# yabc.net
KiCad netlist of a schematic drawn in EAGLE
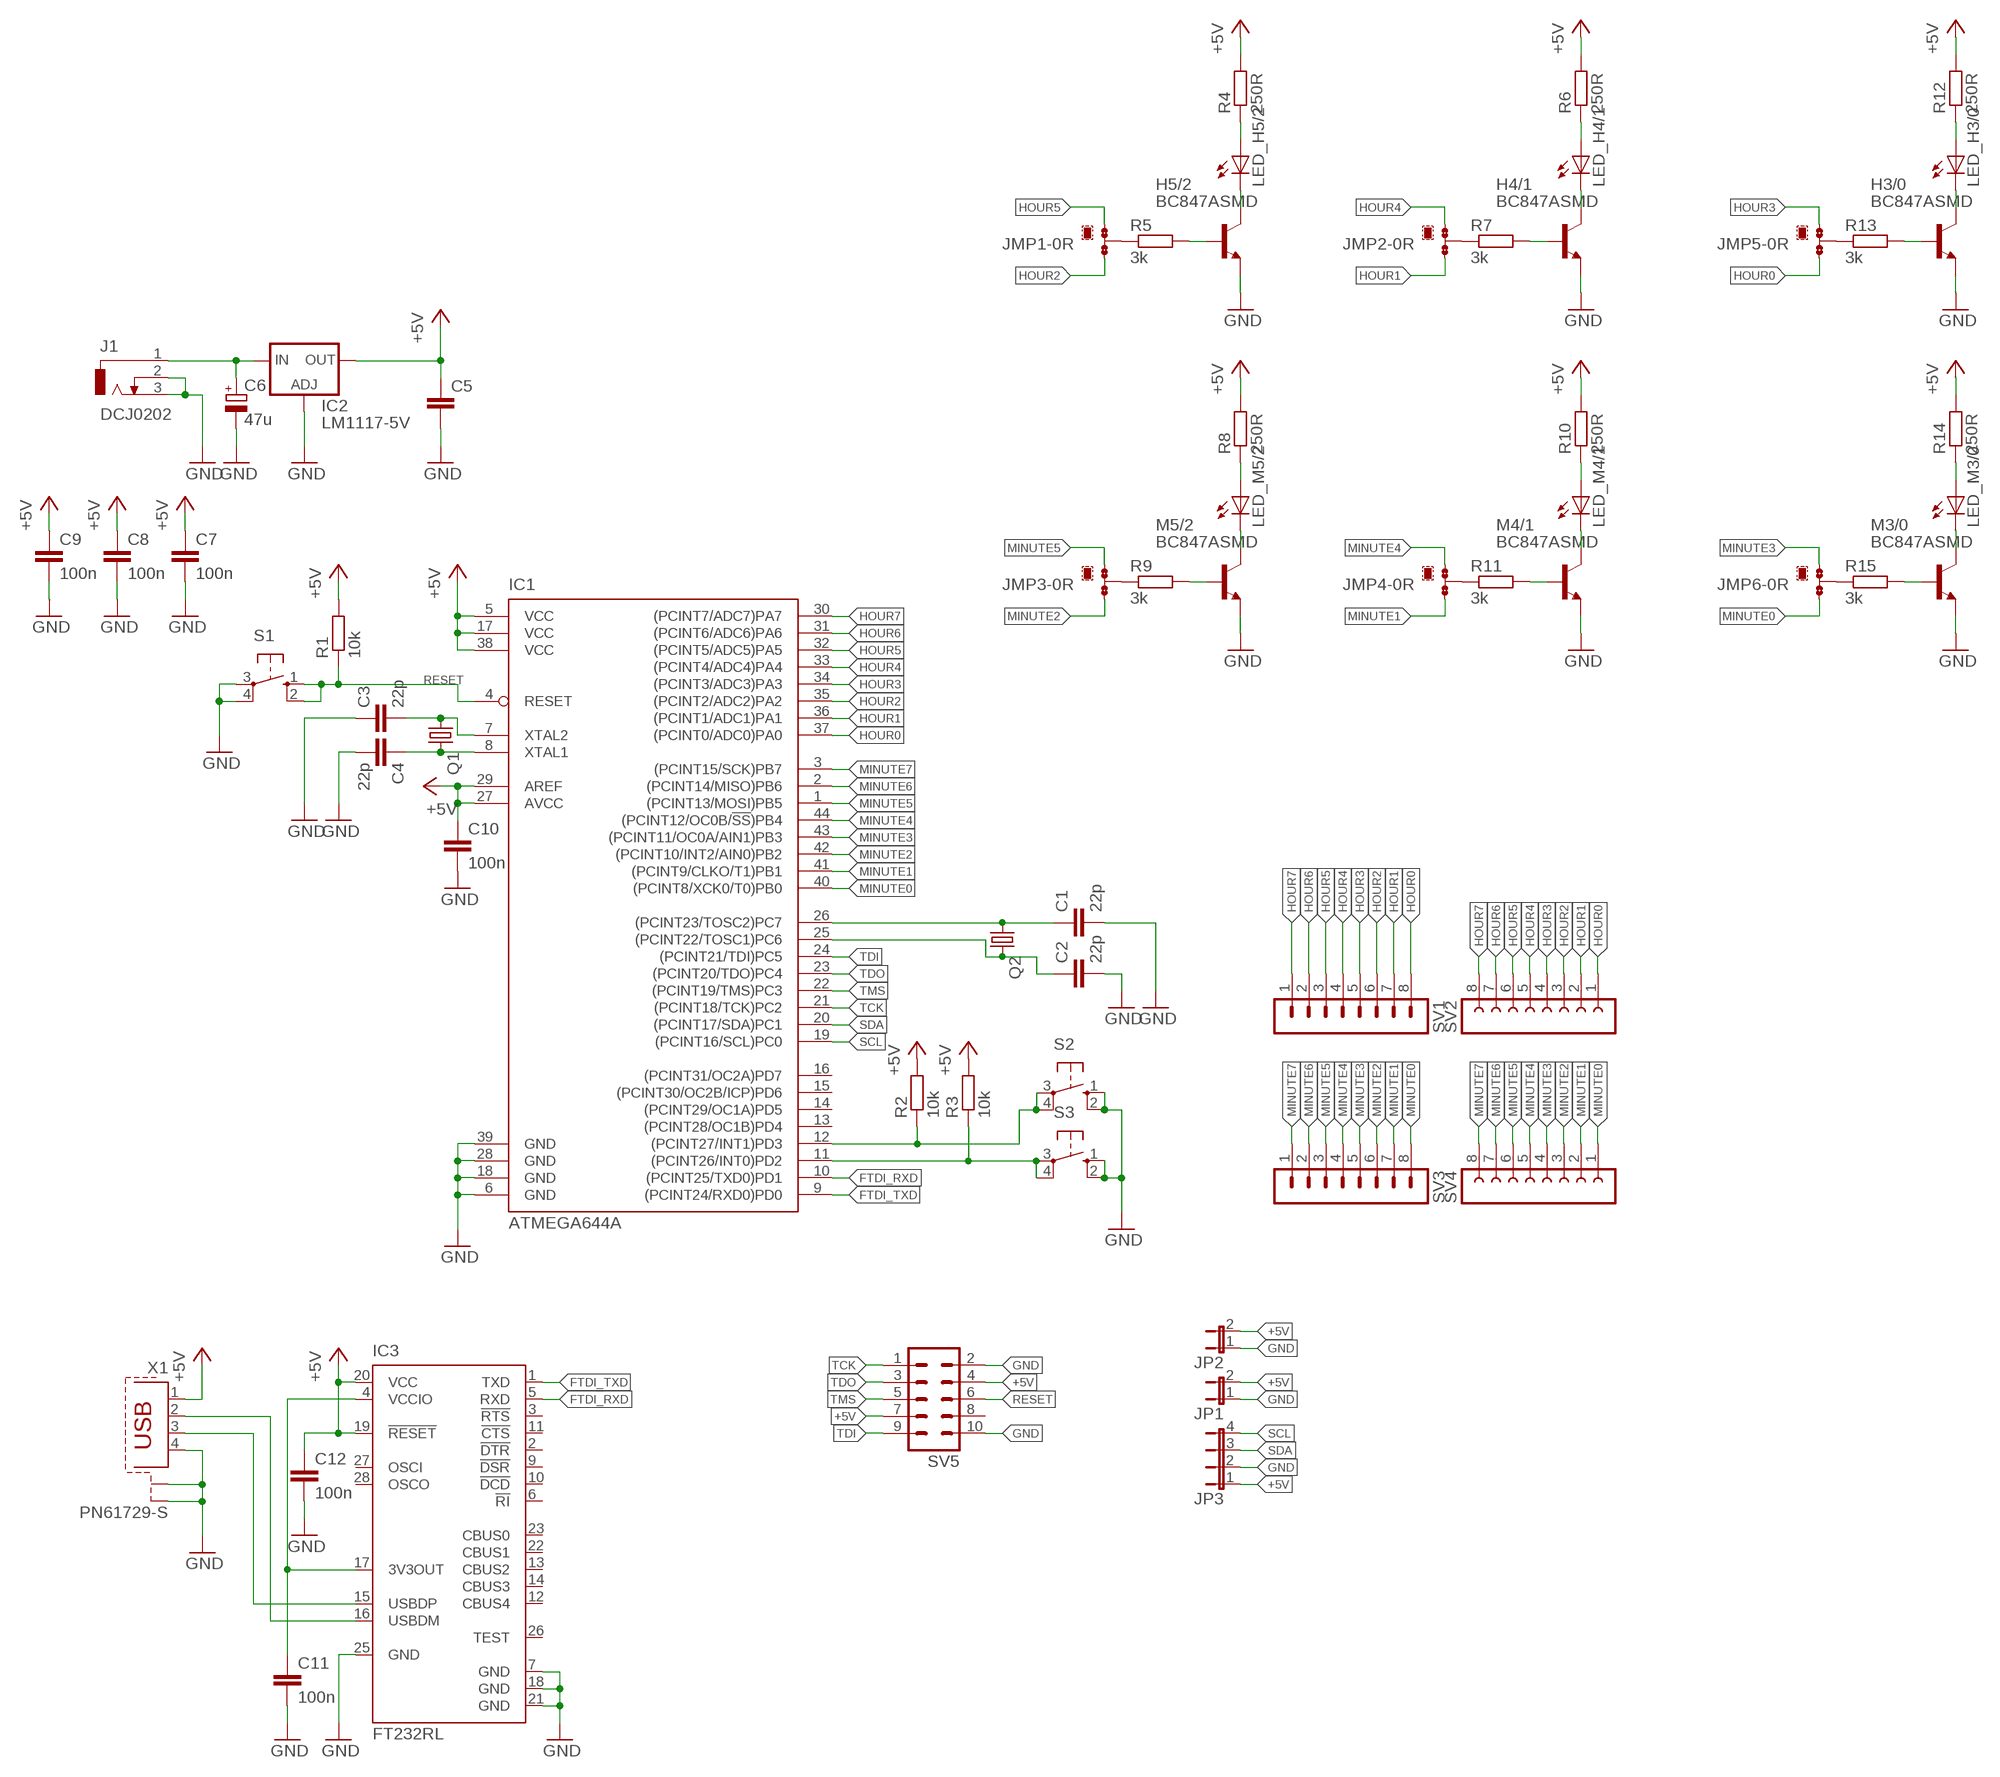
[diagram p0: schematic, sheet 1]

(export (version "E")
  (design (tool "Eeschema 10.0.6"))
  (components
    (comp (ref "C1")
      (value "22p")
      (footprint "eagle-import:C0603")
      (libsource (lib "eagle-import") (part "C-EUC0603"))
    )
    (comp (ref "C2")
      (value "22p")
      (footprint "eagle-import:C0603")
      (libsource (lib "eagle-import") (part "C-EUC0603"))
    )
    (comp (ref "C3")
      (value "22p")
      (footprint "eagle-import:C0603")
      (libsource (lib "eagle-import") (part "C-EUC0603"))
    )
    (comp (ref "C4")
      (value "22p")
      (footprint "eagle-import:C0603")
      (libsource (lib "eagle-import") (part "C-EUC0603"))
    )
    (comp (ref "C5")
      (value "C-EUC0805")
      (footprint "eagle-import:C0805")
      (libsource (lib "eagle-import") (part "C-EUC0805"))
    )
    (comp (ref "C6")
      (value "47u")
      (footprint "eagle-import:SANYO-OSCON_SMD_B6")
      (libsource (lib "eagle-import") (part "CPOL-EUSANYO_SMD_B6"))
    )
    (comp (ref "C7")
      (value "100n")
      (footprint "eagle-import:C0603")
      (libsource (lib "eagle-import") (part "C-EUC0603"))
    )
    (comp (ref "C8")
      (value "100n")
      (footprint "eagle-import:C0603")
      (libsource (lib "eagle-import") (part "C-EUC0603"))
    )
    (comp (ref "C9")
      (value "100n")
      (footprint "eagle-import:C0603")
      (libsource (lib "eagle-import") (part "C-EUC0603"))
    )
    (comp (ref "C10")
      (value "100n")
      (footprint "eagle-import:C0603")
      (libsource (lib "eagle-import") (part "C-EUC0603"))
    )
    (comp (ref "C11")
      (value "100n")
      (footprint "eagle-import:C0603")
      (libsource (lib "eagle-import") (part "C-EUC0603"))
    )
    (comp (ref "C12")
      (value "100n")
      (footprint "eagle-import:C0603")
      (libsource (lib "eagle-import") (part "C-EUC0603"))
    )
    (comp (ref "H3/0")
      (value "BC847ASMD")
      (footprint "eagle-import:SOT23")
      (libsource (lib "eagle-import") (part "BC847SMDA"))
    )
    (comp (ref "H4/1")
      (value "BC847ASMD")
      (footprint "eagle-import:SOT23")
      (libsource (lib "eagle-import") (part "BC847SMDA"))
    )
    (comp (ref "H5/2")
      (value "BC847ASMD")
      (footprint "eagle-import:SOT23")
      (libsource (lib "eagle-import") (part "BC847SMDA"))
    )
    (comp (ref "IC1")
      (value "ATMEGA644A")
      (footprint "eagle-import:TQFP44")
      (fields (field (name "MPN") "ATMEGA644PV-10AU"))
      (libsource (lib "eagle-import") (part "ATMEGA644A"))
    )
    (comp (ref "IC2")
      (value "LM1117-5V")
      (footprint "eagle-import:SOT223")
      (libsource (lib "eagle-import") (part "LM317?MBSTT3"))
    )
    (comp (ref "IC3")
      (value "FT232RL")
      (footprint "eagle-import:SSOP28")
      (libsource (lib "eagle-import") (part "FT232RL"))
    )
    (comp (ref "J1")
      (value "DCJ0202")
      (footprint "eagle-import:DCJ0202")
      (libsource (lib "eagle-import") (part "DCJ0202"))
    )
    (comp (ref "JMP1")
      (value "0R-JUMPC")
      (footprint "eagle-import:C0R-JMP")
      (libsource (lib "eagle-import") (part "0R-JUMPC"))
    )
    (comp (ref "JMP2")
      (value "0R-JUMPC")
      (footprint "eagle-import:C0R-JMP")
      (libsource (lib "eagle-import") (part "0R-JUMPC"))
    )
    (comp (ref "JMP3")
      (value "0R-JUMPC")
      (footprint "eagle-import:C0R-JMP")
      (libsource (lib "eagle-import") (part "0R-JUMPC"))
    )
    (comp (ref "JMP4")
      (value "0R-JUMPC")
      (footprint "eagle-import:C0R-JMP")
      (libsource (lib "eagle-import") (part "0R-JUMPC"))
    )
    (comp (ref "JMP5")
      (value "0R-JUMPC")
      (footprint "eagle-import:C0R-JMP")
      (libsource (lib "eagle-import") (part "0R-JUMPC"))
    )
    (comp (ref "JMP6")
      (value "0R-JUMPC")
      (footprint "eagle-import:C0R-JMP")
      (libsource (lib "eagle-import") (part "0R-JUMPC"))
    )
    (comp (ref "JP1")
      (value "JP1E")
      (footprint "eagle-import:JP1")
      (libsource (lib "eagle-import") (part "JP1E"))
    )
    (comp (ref "JP2")
      (value "JP1E")
      (footprint "eagle-import:JP1")
      (libsource (lib "eagle-import") (part "JP1E"))
    )
    (comp (ref "JP3")
      (value "JP4E")
      (footprint "eagle-import:JP4")
      (libsource (lib "eagle-import") (part "JP4E"))
    )
    (comp (ref "LED_H3/0")
      (value "LED10MM")
      (footprint "eagle-import:LED10MM")
      (libsource (lib "eagle-import") (part "LED10MM"))
    )
    (comp (ref "LED_H4/1")
      (value "LED10MM")
      (footprint "eagle-import:LED10MM")
      (libsource (lib "eagle-import") (part "LED10MM"))
    )
    (comp (ref "LED_H5/2")
      (value "LED10MM")
      (footprint "eagle-import:LED10MM")
      (libsource (lib "eagle-import") (part "LED10MM"))
    )
    (comp (ref "LED_M3/0")
      (value "LED10MM")
      (footprint "eagle-import:LED10MM")
      (libsource (lib "eagle-import") (part "LED10MM"))
    )
    (comp (ref "LED_M4/1")
      (value "LED10MM")
      (footprint "eagle-import:LED10MM")
      (libsource (lib "eagle-import") (part "LED10MM"))
    )
    (comp (ref "LED_M5/2")
      (value "LED10MM")
      (footprint "eagle-import:LED10MM")
      (libsource (lib "eagle-import") (part "LED10MM"))
    )
    (comp (ref "M3/0")
      (value "BC847ASMD")
      (footprint "eagle-import:SOT23")
      (libsource (lib "eagle-import") (part "BC847SMDA"))
    )
    (comp (ref "M4/1")
      (value "BC847ASMD")
      (footprint "eagle-import:SOT23")
      (libsource (lib "eagle-import") (part "BC847SMDA"))
    )
    (comp (ref "M5/2")
      (value "BC847ASMD")
      (footprint "eagle-import:SOT23")
      (libsource (lib "eagle-import") (part "BC847SMDA"))
    )
    (comp (ref "Q1")
      (value "CRYSTALHC49UP")
      (footprint "eagle-import:HC49UP")
      (libsource (lib "eagle-import") (part "CRYSTALHC49UP"))
    )
    (comp (ref "Q2")
      (value "CRYSTALTC26H")
      (footprint "eagle-import:TC26H")
      (libsource (lib "eagle-import") (part "CRYSTALTC26H"))
    )
    (comp (ref "R1")
      (value "10k")
      (footprint "eagle-import:R0603")
      (libsource (lib "eagle-import") (part "R-EU_R0603"))
    )
    (comp (ref "R2")
      (value "10k")
      (footprint "eagle-import:R0603")
      (libsource (lib "eagle-import") (part "R-EU_R0603"))
    )
    (comp (ref "R3")
      (value "10k")
      (footprint "eagle-import:R0603")
      (libsource (lib "eagle-import") (part "R-EU_R0603"))
    )
    (comp (ref "R4")
      (value "250R")
      (footprint "eagle-import:R0805")
      (libsource (lib "eagle-import") (part "R-EU_R0805"))
    )
    (comp (ref "R5")
      (value "3k")
      (footprint "eagle-import:R0603")
      (libsource (lib "eagle-import") (part "R-EU_R0603"))
    )
    (comp (ref "R6")
      (value "250R")
      (footprint "eagle-import:R0805")
      (libsource (lib "eagle-import") (part "R-EU_R0805"))
    )
    (comp (ref "R7")
      (value "3k")
      (footprint "eagle-import:R0603")
      (libsource (lib "eagle-import") (part "R-EU_R0603"))
    )
    (comp (ref "R8")
      (value "250R")
      (footprint "eagle-import:R0805")
      (libsource (lib "eagle-import") (part "R-EU_R0805"))
    )
    (comp (ref "R9")
      (value "3k")
      (footprint "eagle-import:R0603")
      (libsource (lib "eagle-import") (part "R-EU_R0603"))
    )
    (comp (ref "R10")
      (value "250R")
      (footprint "eagle-import:R0805")
      (libsource (lib "eagle-import") (part "R-EU_R0805"))
    )
    (comp (ref "R11")
      (value "3k")
      (footprint "eagle-import:R0603")
      (libsource (lib "eagle-import") (part "R-EU_R0603"))
    )
    (comp (ref "R12")
      (value "250R")
      (footprint "eagle-import:R0805")
      (libsource (lib "eagle-import") (part "R-EU_R0805"))
    )
    (comp (ref "R13")
      (value "3k")
      (footprint "eagle-import:R0603")
      (libsource (lib "eagle-import") (part "R-EU_R0603"))
    )
    (comp (ref "R14")
      (value "250R")
      (footprint "eagle-import:R0805")
      (libsource (lib "eagle-import") (part "R-EU_R0805"))
    )
    (comp (ref "R15")
      (value "3k")
      (footprint "eagle-import:R0603")
      (libsource (lib "eagle-import") (part "R-EU_R0603"))
    )
    (comp (ref "S1")
      (value "10-XX")
      (footprint "eagle-import:B3F-10XX")
      (fields (field (name "MPN") "B3F-1000"))
      (libsource (lib "eagle-import") (part "10-XX"))
    )
    (comp (ref "S2")
      (value "10-XX")
      (footprint "eagle-import:B3F-10XX")
      (fields (field (name "MPN") "B3F-1000"))
      (libsource (lib "eagle-import") (part "10-XX"))
    )
    (comp (ref "S3")
      (value "10-XX")
      (footprint "eagle-import:B3F-10XX")
      (fields (field (name "MPN") "B3F-1000"))
      (libsource (lib "eagle-import") (part "10-XX"))
    )
    (comp (ref "SV1")
      (value "MA08-1W")
      (footprint "eagle-import:MA08-1W")
      (libsource (lib "eagle-import") (part "MA08-1W"))
    )
    (comp (ref "SV2")
      (value "FE08W")
      (footprint "eagle-import:FE08W")
      (libsource (lib "eagle-import") (part "FE08W"))
    )
    (comp (ref "SV3")
      (value "MA08-1W")
      (footprint "eagle-import:MA08-1W")
      (libsource (lib "eagle-import") (part "MA08-1W"))
    )
    (comp (ref "SV4")
      (value "FE08W")
      (footprint "eagle-import:FE08W")
      (libsource (lib "eagle-import") (part "FE08W"))
    )
    (comp (ref "SV5")
      (value "ML10")
      (footprint "eagle-import:ML10")
      (libsource (lib "eagle-import") (part "ML10"))
    )
    (comp (ref "X1")
      (value "PN61729-S")
      (footprint "eagle-import:PN61729-S")
      (libsource (lib "eagle-import") (part "PN61729-S"))
    )
  )
  (nets
    (net (code "1") (name "+5V") (class "Default")
      (node (ref "C10") (pin "1") (pinfunction "1_1") (pintype "passive"))
      (node (ref "C12") (pin "1") (pinfunction "1_1") (pintype "passive"))
      (node (ref "C5") (pin "1") (pinfunction "1_1") (pintype "passive"))
      (node (ref "C7") (pin "1") (pinfunction "1_1") (pintype "passive"))
      (node (ref "C8") (pin "1") (pinfunction "1_1") (pintype "passive"))
      (node (ref "C9") (pin "1") (pinfunction "1_1") (pintype "passive"))
      (node (ref "IC1") (pin "17") (pinfunction "VCC_17") (pintype "power_in"))
      (node (ref "IC1") (pin "27") (pinfunction "AVCC_27") (pintype "power_in"))
      (node (ref "IC1") (pin "29") (pinfunction "AREF_29") (pintype "passive"))
      (node (ref "IC1") (pin "38") (pinfunction "VCC_38") (pintype "power_in"))
      (node (ref "IC1") (pin "5") (pinfunction "VCC_5") (pintype "power_in"))
      (node (ref "IC2") (pin "4") (pinfunction "OUT_4") (pintype "passive"))
      (node (ref "IC3") (pin "19") (pinfunction "~{RESET}_19") (pintype "input"))
      (node (ref "IC3") (pin "20") (pinfunction "VCC_20") (pintype "power_in"))
      (node (ref "JP1") (pin "2") (pinfunction "2_2") (pintype "passive"))
      (node (ref "JP2") (pin "2") (pinfunction "2_2") (pintype "passive"))
      (node (ref "JP3") (pin "1") (pinfunction "1_1") (pintype "passive"))
      (node (ref "R1") (pin "2") (pinfunction "2_2") (pintype "passive"))
      (node (ref "R10") (pin "2") (pinfunction "2_2") (pintype "passive"))
      (node (ref "R12") (pin "2") (pinfunction "2_2") (pintype "passive"))
      (node (ref "R14") (pin "2") (pinfunction "2_2") (pintype "passive"))
      (node (ref "R2") (pin "2") (pinfunction "2_2") (pintype "passive"))
      (node (ref "R3") (pin "2") (pinfunction "2_2") (pintype "passive"))
      (node (ref "R4") (pin "2") (pinfunction "2_2") (pintype "passive"))
      (node (ref "R6") (pin "2") (pinfunction "2_2") (pintype "passive"))
      (node (ref "R8") (pin "2") (pinfunction "2_2") (pintype "passive"))
      (node (ref "SV5") (pin "4") (pinfunction "4_4") (pintype "passive"))
      (node (ref "SV5") (pin "7") (pinfunction "7_7") (pintype "passive"))
      (node (ref "X1") (pin "1") (pinfunction "1_1") (pintype "passive"))
    )
    (net (code "2") (name "FTDI_RXD") (class "Default")
      (node (ref "IC1") (pin "10") (pinfunction "(PCINT25/TXD0)PD1_10") (pintype "bidirectional"))
      (node (ref "IC3") (pin "5") (pinfunction "RXD_5") (pintype "input"))
    )
    (net (code "3") (name "FTDI_TXD") (class "Default")
      (node (ref "IC1") (pin "9") (pinfunction "(PCINT24/RXD0)PD0_9") (pintype "bidirectional"))
      (node (ref "IC3") (pin "1") (pinfunction "TXD_1") (pintype "output"))
    )
    (net (code "4") (name "GND") (class "Default")
      (node (ref "C1") (pin "2") (pinfunction "2_2") (pintype "passive"))
      (node (ref "C10") (pin "2") (pinfunction "2_2") (pintype "passive"))
      (node (ref "C11") (pin "2") (pinfunction "2_2") (pintype "passive"))
      (node (ref "C12") (pin "2") (pinfunction "2_2") (pintype "passive"))
      (node (ref "C2") (pin "2") (pinfunction "2_2") (pintype "passive"))
      (node (ref "C3") (pin "1") (pinfunction "1_1") (pintype "passive"))
      (node (ref "C4") (pin "2") (pinfunction "2_2") (pintype "passive"))
      (node (ref "C5") (pin "2") (pinfunction "2_2") (pintype "passive"))
      (node (ref "C6") (pin "-") (pinfunction "-_-") (pintype "passive"))
      (node (ref "C7") (pin "2") (pinfunction "2_2") (pintype "passive"))
      (node (ref "C8") (pin "2") (pinfunction "2_2") (pintype "passive"))
      (node (ref "C9") (pin "2") (pinfunction "2_2") (pintype "passive"))
      (node (ref "H3/0") (pin "2") (pinfunction "E_2") (pintype "passive"))
      (node (ref "H4/1") (pin "2") (pinfunction "E_2") (pintype "passive"))
      (node (ref "H5/2") (pin "2") (pinfunction "E_2") (pintype "passive"))
      (node (ref "IC1") (pin "18") (pinfunction "GND_18") (pintype "power_in"))
      (node (ref "IC1") (pin "28") (pinfunction "GND_28") (pintype "power_in"))
      (node (ref "IC1") (pin "39") (pinfunction "GND_39") (pintype "power_in"))
      (node (ref "IC1") (pin "6") (pinfunction "GND_6") (pintype "power_in"))
      (node (ref "IC2") (pin "1") (pinfunction "ADJ_1") (pintype "input"))
      (node (ref "IC3") (pin "18") (pinfunction "GND_18") (pintype "power_in"))
      (node (ref "IC3") (pin "21") (pinfunction "GND_21") (pintype "power_in"))
      (node (ref "IC3") (pin "25") (pinfunction "GND_25") (pintype "power_in"))
      (node (ref "IC3") (pin "7") (pinfunction "GND_7") (pintype "power_in"))
      (node (ref "J1") (pin "2") (pinfunction "2_2") (pintype "passive"))
      (node (ref "J1") (pin "3") (pinfunction "3_3") (pintype "passive"))
      (node (ref "JP1") (pin "1") (pinfunction "1_1") (pintype "passive"))
      (node (ref "JP2") (pin "1") (pinfunction "1_1") (pintype "passive"))
      (node (ref "JP3") (pin "2") (pinfunction "2_2") (pintype "passive"))
      (node (ref "M3/0") (pin "2") (pinfunction "E_2") (pintype "passive"))
      (node (ref "M4/1") (pin "2") (pinfunction "E_2") (pintype "passive"))
      (node (ref "M5/2") (pin "2") (pinfunction "E_2") (pintype "passive"))
      (node (ref "S1") (pin "3") (pinfunction "P_3") (pintype "passive"))
      (node (ref "S1") (pin "4") (pinfunction "P1_4") (pintype "passive"))
      (node (ref "S2") (pin "1") (pinfunction "S_1") (pintype "passive"))
      (node (ref "S2") (pin "2") (pinfunction "S1_2") (pintype "passive"))
      (node (ref "S3") (pin "1") (pinfunction "S_1") (pintype "passive"))
      (node (ref "S3") (pin "2") (pinfunction "S1_2") (pintype "passive"))
      (node (ref "SV5") (pin "10") (pinfunction "10_10") (pintype "passive"))
      (node (ref "SV5") (pin "2") (pinfunction "2_2") (pintype "passive"))
      (node (ref "X1") (pin "4") (pinfunction "4_4") (pintype "passive"))
      (node (ref "X1") (pin "S1") (pinfunction "S1_S1") (pintype "passive"))
      (node (ref "X1") (pin "S2") (pinfunction "S2_S2") (pintype "passive"))
    )
    (net (code "5") (name "HOUR0") (class "Default")
      (node (ref "IC1") (pin "37") (pinfunction "(PCINT0/ADC0)PA0_37") (pintype "bidirectional"))
      (node (ref "JMP5") (pin "3") (pinfunction "3_3") (pintype "passive"))
      (node (ref "SV1") (pin "8") (pinfunction "8_8") (pintype "passive"))
      (node (ref "SV2") (pin "1") (pinfunction "1_1") (pintype "passive"))
    )
    (net (code "6") (name "HOUR1") (class "Default")
      (node (ref "IC1") (pin "36") (pinfunction "(PCINT1/ADC1)PA1_36") (pintype "bidirectional"))
      (node (ref "JMP2") (pin "3") (pinfunction "3_3") (pintype "passive"))
      (node (ref "SV1") (pin "7") (pinfunction "7_7") (pintype "passive"))
      (node (ref "SV2") (pin "2") (pinfunction "2_2") (pintype "passive"))
    )
    (net (code "7") (name "HOUR2") (class "Default")
      (node (ref "IC1") (pin "35") (pinfunction "(PCINT2/ADC2)PA2_35") (pintype "bidirectional"))
      (node (ref "JMP1") (pin "3") (pinfunction "3_3") (pintype "passive"))
      (node (ref "SV1") (pin "6") (pinfunction "6_6") (pintype "passive"))
      (node (ref "SV2") (pin "3") (pinfunction "3_3") (pintype "passive"))
    )
    (net (code "8") (name "HOUR3") (class "Default")
      (node (ref "IC1") (pin "34") (pinfunction "(PCINT3/ADC3)PA3_34") (pintype "bidirectional"))
      (node (ref "JMP5") (pin "1") (pinfunction "1_1") (pintype "passive"))
      (node (ref "SV1") (pin "5") (pinfunction "5_5") (pintype "passive"))
      (node (ref "SV2") (pin "4") (pinfunction "4_4") (pintype "passive"))
    )
    (net (code "9") (name "HOUR4") (class "Default")
      (node (ref "IC1") (pin "33") (pinfunction "(PCINT4/ADC4)PA4_33") (pintype "bidirectional"))
      (node (ref "JMP2") (pin "1") (pinfunction "1_1") (pintype "passive"))
      (node (ref "SV1") (pin "4") (pinfunction "4_4") (pintype "passive"))
      (node (ref "SV2") (pin "5") (pinfunction "5_5") (pintype "passive"))
    )
    (net (code "10") (name "HOUR5") (class "Default")
      (node (ref "IC1") (pin "32") (pinfunction "(PCINT5/ADC5)PA5_32") (pintype "bidirectional"))
      (node (ref "JMP1") (pin "1") (pinfunction "1_1") (pintype "passive"))
      (node (ref "SV1") (pin "3") (pinfunction "3_3") (pintype "passive"))
      (node (ref "SV2") (pin "6") (pinfunction "6_6") (pintype "passive"))
    )
    (net (code "11") (name "HOUR6") (class "Default")
      (node (ref "IC1") (pin "31") (pinfunction "(PCINT6/ADC6)PA6_31") (pintype "bidirectional"))
      (node (ref "SV1") (pin "2") (pinfunction "2_2") (pintype "passive"))
      (node (ref "SV2") (pin "7") (pinfunction "7_7") (pintype "passive"))
    )
    (net (code "12") (name "HOUR7") (class "Default")
      (node (ref "IC1") (pin "30") (pinfunction "(PCINT7/ADC7)PA7_30") (pintype "bidirectional"))
      (node (ref "SV1") (pin "1") (pinfunction "1_1") (pintype "passive"))
      (node (ref "SV2") (pin "8") (pinfunction "8_8") (pintype "passive"))
    )
    (net (code "13") (name "MINUTE0") (class "Default")
      (node (ref "IC1") (pin "40") (pinfunction "(PCINT8/XCK0/T0)PB0_40") (pintype "bidirectional"))
      (node (ref "JMP6") (pin "3") (pinfunction "3_3") (pintype "passive"))
      (node (ref "SV3") (pin "8") (pinfunction "8_8") (pintype "passive"))
      (node (ref "SV4") (pin "1") (pinfunction "1_1") (pintype "passive"))
    )
    (net (code "14") (name "MINUTE1") (class "Default")
      (node (ref "IC1") (pin "41") (pinfunction "(PCINT9/CLKO/T1)PB1_41") (pintype "bidirectional"))
      (node (ref "JMP4") (pin "3") (pinfunction "3_3") (pintype "passive"))
      (node (ref "SV3") (pin "7") (pinfunction "7_7") (pintype "passive"))
      (node (ref "SV4") (pin "2") (pinfunction "2_2") (pintype "passive"))
    )
    (net (code "15") (name "MINUTE2") (class "Default")
      (node (ref "IC1") (pin "42") (pinfunction "(PCINT10/INT2/AIN0)PB2_42") (pintype "bidirectional"))
      (node (ref "JMP3") (pin "3") (pinfunction "3_3") (pintype "passive"))
      (node (ref "SV3") (pin "6") (pinfunction "6_6") (pintype "passive"))
      (node (ref "SV4") (pin "3") (pinfunction "3_3") (pintype "passive"))
    )
    (net (code "16") (name "MINUTE3") (class "Default")
      (node (ref "IC1") (pin "43") (pinfunction "(PCINT11/OC0A/AIN1)PB3_43") (pintype "bidirectional"))
      (node (ref "JMP6") (pin "1") (pinfunction "1_1") (pintype "passive"))
      (node (ref "SV3") (pin "5") (pinfunction "5_5") (pintype "passive"))
      (node (ref "SV4") (pin "4") (pinfunction "4_4") (pintype "passive"))
    )
    (net (code "17") (name "MINUTE4") (class "Default")
      (node (ref "IC1") (pin "44") (pinfunction "(PCINT12/OC0B/~{SS})PB4_44") (pintype "bidirectional"))
      (node (ref "JMP4") (pin "1") (pinfunction "1_1") (pintype "passive"))
      (node (ref "SV3") (pin "4") (pinfunction "4_4") (pintype "passive"))
      (node (ref "SV4") (pin "5") (pinfunction "5_5") (pintype "passive"))
    )
    (net (code "18") (name "MINUTE5") (class "Default")
      (node (ref "IC1") (pin "1") (pinfunction "(PCINT13/MOSI)PB5_1") (pintype "bidirectional"))
      (node (ref "JMP3") (pin "1") (pinfunction "1_1") (pintype "passive"))
      (node (ref "SV3") (pin "3") (pinfunction "3_3") (pintype "passive"))
      (node (ref "SV4") (pin "6") (pinfunction "6_6") (pintype "passive"))
    )
    (net (code "19") (name "MINUTE6") (class "Default")
      (node (ref "IC1") (pin "2") (pinfunction "(PCINT14/MISO)PB6_2") (pintype "bidirectional"))
      (node (ref "SV3") (pin "2") (pinfunction "2_2") (pintype "passive"))
      (node (ref "SV4") (pin "7") (pinfunction "7_7") (pintype "passive"))
    )
    (net (code "20") (name "MINUTE7") (class "Default")
      (node (ref "IC1") (pin "3") (pinfunction "(PCINT15/SCK)PB7_3") (pintype "bidirectional"))
      (node (ref "SV3") (pin "1") (pinfunction "1_1") (pintype "passive"))
      (node (ref "SV4") (pin "8") (pinfunction "8_8") (pintype "passive"))
    )
    (net (code "21") (name "Net-(H3/0-B)") (class "Default")
      (node (ref "H3/0") (pin "1") (pinfunction "B_1") (pintype "passive"))
      (node (ref "R13") (pin "2") (pinfunction "2_2") (pintype "passive"))
    )
    (net (code "22") (name "Net-(H3/0-C)") (class "Default")
      (node (ref "H3/0") (pin "3") (pinfunction "C_3") (pintype "passive"))
      (node (ref "LED_H3/0") (pin "K") (pinfunction "C_K") (pintype "passive"))
    )
    (net (code "23") (name "Net-(H4/1-B)") (class "Default")
      (node (ref "H4/1") (pin "1") (pinfunction "B_1") (pintype "passive"))
      (node (ref "R7") (pin "2") (pinfunction "2_2") (pintype "passive"))
    )
    (net (code "24") (name "Net-(H4/1-C)") (class "Default")
      (node (ref "H4/1") (pin "3") (pinfunction "C_3") (pintype "passive"))
      (node (ref "LED_H4/1") (pin "K") (pinfunction "C_K") (pintype "passive"))
    )
    (net (code "25") (name "Net-(H5/2-B)") (class "Default")
      (node (ref "H5/2") (pin "1") (pinfunction "B_1") (pintype "passive"))
      (node (ref "R5") (pin "2") (pinfunction "2_2") (pintype "passive"))
    )
    (net (code "26") (name "Net-(H5/2-C)") (class "Default")
      (node (ref "H5/2") (pin "3") (pinfunction "C_3") (pintype "passive"))
      (node (ref "LED_H5/2") (pin "K") (pinfunction "C_K") (pintype "passive"))
    )
    (net (code "27") (name "Net-(IC1-(PCINT22{slash}TOSC1)PC6)") (class "Default")
      (node (ref "C2") (pin "1") (pinfunction "1_1") (pintype "passive"))
      (node (ref "IC1") (pin "25") (pinfunction "(PCINT22/TOSC1)PC6_25") (pintype "output"))
      (node (ref "Q2") (pin "2") (pinfunction "2_2") (pintype "passive"))
    )
    (net (code "28") (name "Net-(IC1-(PCINT23{slash}TOSC2)PC7)") (class "Default")
      (node (ref "C1") (pin "1") (pinfunction "1_1") (pintype "passive"))
      (node (ref "IC1") (pin "26") (pinfunction "(PCINT23/TOSC2)PC7_26") (pintype "output"))
      (node (ref "Q2") (pin "1") (pinfunction "1_1") (pintype "passive"))
    )
    (net (code "29") (name "Net-(IC1-(PCINT26{slash}INT0)PD2)") (class "Default")
      (node (ref "IC1") (pin "11") (pinfunction "(PCINT26/INT0)PD2_11") (pintype "bidirectional"))
      (node (ref "R3") (pin "1") (pinfunction "1_1") (pintype "passive"))
      (node (ref "S3") (pin "3") (pinfunction "P_3") (pintype "passive"))
      (node (ref "S3") (pin "4") (pinfunction "P1_4") (pintype "passive"))
    )
    (net (code "30") (name "Net-(IC1-(PCINT27{slash}INT1)PD3)") (class "Default")
      (node (ref "IC1") (pin "12") (pinfunction "(PCINT27/INT1)PD3_12") (pintype "bidirectional"))
      (node (ref "R2") (pin "1") (pinfunction "1_1") (pintype "passive"))
      (node (ref "S2") (pin "3") (pinfunction "P_3") (pintype "passive"))
      (node (ref "S2") (pin "4") (pinfunction "P1_4") (pintype "passive"))
    )
    (net (code "31") (name "Net-(IC1-XTAL1)") (class "Default")
      (node (ref "C4") (pin "1") (pinfunction "1_1") (pintype "passive"))
      (node (ref "IC1") (pin "8") (pinfunction "XTAL1_8") (pintype "bidirectional"))
      (node (ref "Q1") (pin "2") (pinfunction "2_2") (pintype "passive"))
    )
    (net (code "32") (name "Net-(IC1-XTAL2)") (class "Default")
      (node (ref "C3") (pin "2") (pinfunction "2_2") (pintype "passive"))
      (node (ref "IC1") (pin "7") (pinfunction "XTAL2_7") (pintype "bidirectional"))
      (node (ref "Q1") (pin "1") (pinfunction "1_1") (pintype "passive"))
    )
    (net (code "33") (name "Net-(IC2-IN)") (class "Default")
      (node (ref "C6") (pin "+") (pinfunction "+_+") (pintype "passive"))
      (node (ref "IC2") (pin "3") (pinfunction "IN_3") (pintype "input"))
      (node (ref "J1") (pin "1") (pinfunction "1_1") (pintype "passive"))
    )
    (net (code "34") (name "Net-(IC3-3V3OUT)") (class "Default")
      (node (ref "C11") (pin "1") (pinfunction "1_1") (pintype "passive"))
      (node (ref "IC3") (pin "17") (pinfunction "3V3OUT_17") (pintype "output"))
      (node (ref "IC3") (pin "4") (pinfunction "VCCIO_4") (pintype "power_in"))
    )
    (net (code "35") (name "Net-(IC3-USBDM)") (class "Default")
      (node (ref "IC3") (pin "16") (pinfunction "USBDM_16") (pintype "bidirectional"))
      (node (ref "X1") (pin "2") (pinfunction "2_2") (pintype "passive"))
    )
    (net (code "36") (name "Net-(IC3-USBDP)") (class "Default")
      (node (ref "IC3") (pin "15") (pinfunction "USBDP_15") (pintype "bidirectional"))
      (node (ref "X1") (pin "3") (pinfunction "3_3") (pintype "passive"))
    )
    (net (code "37") (name "Net-(JMP1-Pad2)") (class "Default")
      (node (ref "JMP1") (pin "2") (pinfunction "2_2") (pintype "passive"))
      (node (ref "R5") (pin "1") (pinfunction "1_1") (pintype "passive"))
    )
    (net (code "38") (name "Net-(JMP2-Pad2)") (class "Default")
      (node (ref "JMP2") (pin "2") (pinfunction "2_2") (pintype "passive"))
      (node (ref "R7") (pin "1") (pinfunction "1_1") (pintype "passive"))
    )
    (net (code "39") (name "Net-(JMP3-Pad2)") (class "Default")
      (node (ref "JMP3") (pin "2") (pinfunction "2_2") (pintype "passive"))
      (node (ref "R9") (pin "1") (pinfunction "1_1") (pintype "passive"))
    )
    (net (code "40") (name "Net-(JMP4-Pad2)") (class "Default")
      (node (ref "JMP4") (pin "2") (pinfunction "2_2") (pintype "passive"))
      (node (ref "R11") (pin "1") (pinfunction "1_1") (pintype "passive"))
    )
    (net (code "41") (name "Net-(JMP5-Pad2)") (class "Default")
      (node (ref "JMP5") (pin "2") (pinfunction "2_2") (pintype "passive"))
      (node (ref "R13") (pin "1") (pinfunction "1_1") (pintype "passive"))
    )
    (net (code "42") (name "Net-(JMP6-Pad2)") (class "Default")
      (node (ref "JMP6") (pin "2") (pinfunction "2_2") (pintype "passive"))
      (node (ref "R15") (pin "1") (pinfunction "1_1") (pintype "passive"))
    )
    (net (code "43") (name "Net-(LED_H3/0-PadA)") (class "Default")
      (node (ref "LED_H3/0") (pin "A") (pinfunction "A_A") (pintype "passive"))
      (node (ref "R12") (pin "1") (pinfunction "1_1") (pintype "passive"))
    )
    (net (code "44") (name "Net-(LED_H4/1-PadA)") (class "Default")
      (node (ref "LED_H4/1") (pin "A") (pinfunction "A_A") (pintype "passive"))
      (node (ref "R6") (pin "1") (pinfunction "1_1") (pintype "passive"))
    )
    (net (code "45") (name "Net-(LED_H5/2-PadA)") (class "Default")
      (node (ref "LED_H5/2") (pin "A") (pinfunction "A_A") (pintype "passive"))
      (node (ref "R4") (pin "1") (pinfunction "1_1") (pintype "passive"))
    )
    (net (code "46") (name "Net-(LED_M3/0-C)") (class "Default")
      (node (ref "LED_M3/0") (pin "K") (pinfunction "C_K") (pintype "passive"))
      (node (ref "M3/0") (pin "3") (pinfunction "C_3") (pintype "passive"))
    )
    (net (code "47") (name "Net-(LED_M3/0-PadA)") (class "Default")
      (node (ref "LED_M3/0") (pin "A") (pinfunction "A_A") (pintype "passive"))
      (node (ref "R14") (pin "1") (pinfunction "1_1") (pintype "passive"))
    )
    (net (code "48") (name "Net-(LED_M4/1-C)") (class "Default")
      (node (ref "LED_M4/1") (pin "K") (pinfunction "C_K") (pintype "passive"))
      (node (ref "M4/1") (pin "3") (pinfunction "C_3") (pintype "passive"))
    )
    (net (code "49") (name "Net-(LED_M4/1-PadA)") (class "Default")
      (node (ref "LED_M4/1") (pin "A") (pinfunction "A_A") (pintype "passive"))
      (node (ref "R10") (pin "1") (pinfunction "1_1") (pintype "passive"))
    )
    (net (code "50") (name "Net-(LED_M5/2-C)") (class "Default")
      (node (ref "LED_M5/2") (pin "K") (pinfunction "C_K") (pintype "passive"))
      (node (ref "M5/2") (pin "3") (pinfunction "C_3") (pintype "passive"))
    )
    (net (code "51") (name "Net-(LED_M5/2-PadA)") (class "Default")
      (node (ref "LED_M5/2") (pin "A") (pinfunction "A_A") (pintype "passive"))
      (node (ref "R8") (pin "1") (pinfunction "1_1") (pintype "passive"))
    )
    (net (code "52") (name "Net-(M3/0-B)") (class "Default")
      (node (ref "M3/0") (pin "1") (pinfunction "B_1") (pintype "passive"))
      (node (ref "R15") (pin "2") (pinfunction "2_2") (pintype "passive"))
    )
    (net (code "53") (name "Net-(M4/1-B)") (class "Default")
      (node (ref "M4/1") (pin "1") (pinfunction "B_1") (pintype "passive"))
      (node (ref "R11") (pin "2") (pinfunction "2_2") (pintype "passive"))
    )
    (net (code "54") (name "Net-(M5/2-B)") (class "Default")
      (node (ref "M5/2") (pin "1") (pinfunction "B_1") (pintype "passive"))
      (node (ref "R9") (pin "2") (pinfunction "2_2") (pintype "passive"))
    )
    (net (code "55") (name "RESET") (class "Default")
      (node (ref "IC1") (pin "4") (pinfunction "RESET_4") (pintype "input"))
      (node (ref "R1") (pin "1") (pinfunction "1_1") (pintype "passive"))
      (node (ref "S1") (pin "1") (pinfunction "S_1") (pintype "passive"))
      (node (ref "S1") (pin "2") (pinfunction "S1_2") (pintype "passive"))
      (node (ref "SV5") (pin "6") (pinfunction "6_6") (pintype "passive"))
    )
    (net (code "56") (name "SCL") (class "Default")
      (node (ref "IC1") (pin "19") (pinfunction "(PCINT16/SCL)PC0_19") (pintype "output"))
      (node (ref "JP3") (pin "4") (pinfunction "4_4") (pintype "passive"))
    )
    (net (code "57") (name "SDA") (class "Default")
      (node (ref "IC1") (pin "20") (pinfunction "(PCINT17/SDA)PC1_20") (pintype "output"))
      (node (ref "JP3") (pin "3") (pinfunction "3_3") (pintype "passive"))
    )
    (net (code "58") (name "TCK") (class "Default")
      (node (ref "IC1") (pin "21") (pinfunction "(PCINT18/TCK)PC2_21") (pintype "output"))
      (node (ref "SV5") (pin "1") (pinfunction "1_1") (pintype "passive"))
    )
    (net (code "59") (name "TDI") (class "Default")
      (node (ref "IC1") (pin "24") (pinfunction "(PCINT21/TDI)PC5_24") (pintype "output"))
      (node (ref "SV5") (pin "9") (pinfunction "9_9") (pintype "passive"))
    )
    (net (code "60") (name "TDO") (class "Default")
      (node (ref "IC1") (pin "23") (pinfunction "(PCINT20/TDO)PC4_23") (pintype "output"))
      (node (ref "SV5") (pin "3") (pinfunction "3_3") (pintype "passive"))
    )
    (net (code "61") (name "TMS") (class "Default")
      (node (ref "IC1") (pin "22") (pinfunction "(PCINT19/TMS)PC3_22") (pintype "output"))
      (node (ref "SV5") (pin "5") (pinfunction "5_5") (pintype "passive"))
    )
    (net (code "62") (name "unconnected-(IC1-(PCINT28{slash}OC1B)PD4-Pad13)") (class "Default")
      (node (ref "IC1") (pin "13") (pinfunction "(PCINT28/OC1B)PD4_13") (pintype "bidirectional"))
    )
    (net (code "63") (name "unconnected-(IC1-(PCINT29{slash}OC1A)PD5-Pad14)") (class "Default")
      (node (ref "IC1") (pin "14") (pinfunction "(PCINT29/OC1A)PD5_14") (pintype "bidirectional"))
    )
    (net (code "64") (name "unconnected-(IC1-(PCINT30{slash}OC2B{slash}ICP)PD6-Pad15)") (class "Default")
      (node (ref "IC1") (pin "15") (pinfunction "(PCINT30/OC2B/ICP)PD6_15") (pintype "bidirectional"))
    )
    (net (code "65") (name "unconnected-(IC1-(PCINT31{slash}OC2A)PD7-Pad16)") (class "Default")
      (node (ref "IC1") (pin "16") (pinfunction "(PCINT31/OC2A)PD7_16") (pintype "bidirectional"))
    )
    (net (code "66") (name "unconnected-(IC3-CBUS0-Pad23)") (class "Default")
      (node (ref "IC3") (pin "23") (pinfunction "CBUS0_23") (pintype "bidirectional"))
    )
    (net (code "67") (name "unconnected-(IC3-CBUS1-Pad22)") (class "Default")
      (node (ref "IC3") (pin "22") (pinfunction "CBUS1_22") (pintype "bidirectional"))
    )
    (net (code "68") (name "unconnected-(IC3-CBUS2-Pad13)") (class "Default")
      (node (ref "IC3") (pin "13") (pinfunction "CBUS2_13") (pintype "bidirectional"))
    )
    (net (code "69") (name "unconnected-(IC3-CBUS3-Pad14)") (class "Default")
      (node (ref "IC3") (pin "14") (pinfunction "CBUS3_14") (pintype "bidirectional"))
    )
    (net (code "70") (name "unconnected-(IC3-CBUS4-Pad12)") (class "Default")
      (node (ref "IC3") (pin "12") (pinfunction "CBUS4_12") (pintype "bidirectional"))
    )
    (net (code "71") (name "unconnected-(IC3-OSCI-Pad27)") (class "Default")
      (node (ref "IC3") (pin "27") (pinfunction "OSCI_27") (pintype "input"))
    )
    (net (code "72") (name "unconnected-(IC3-OSCO-Pad28)") (class "Default")
      (node (ref "IC3") (pin "28") (pinfunction "OSCO_28") (pintype "output"))
    )
    (net (code "73") (name "unconnected-(IC3-TEST-Pad26)") (class "Default")
      (node (ref "IC3") (pin "26") (pinfunction "TEST_26") (pintype "input"))
    )
    (net (code "74") (name "unconnected-(IC3-~{CTS}-Pad11)") (class "Default")
      (node (ref "IC3") (pin "11") (pinfunction "~{CTS}_11") (pintype "input"))
    )
    (net (code "75") (name "unconnected-(IC3-~{DCD}-Pad10)") (class "Default")
      (node (ref "IC3") (pin "10") (pinfunction "~{DCD}_10") (pintype "input"))
    )
    (net (code "76") (name "unconnected-(IC3-~{DSR}-Pad9)") (class "Default")
      (node (ref "IC3") (pin "9") (pinfunction "~{DSR}_9") (pintype "input"))
    )
    (net (code "77") (name "unconnected-(IC3-~{DTR}-Pad2)") (class "Default")
      (node (ref "IC3") (pin "2") (pinfunction "~{DTR}_2") (pintype "output"))
    )
    (net (code "78") (name "unconnected-(IC3-~{RI}-Pad6)") (class "Default")
      (node (ref "IC3") (pin "6") (pinfunction "~{RI}_6") (pintype "input"))
    )
    (net (code "79") (name "unconnected-(IC3-~{RTS}-Pad3)") (class "Default")
      (node (ref "IC3") (pin "3") (pinfunction "~{RTS}_3") (pintype "output"))
    )
    (net (code "80") (name "unconnected-(SV5-Pad8)") (class "Default")
      (node (ref "SV5") (pin "8") (pinfunction "8_8") (pintype "passive"))
    )
  )
)
